# Flyback_SMPS.net
KiCad netlist of a schematic drawn in Altium Designer
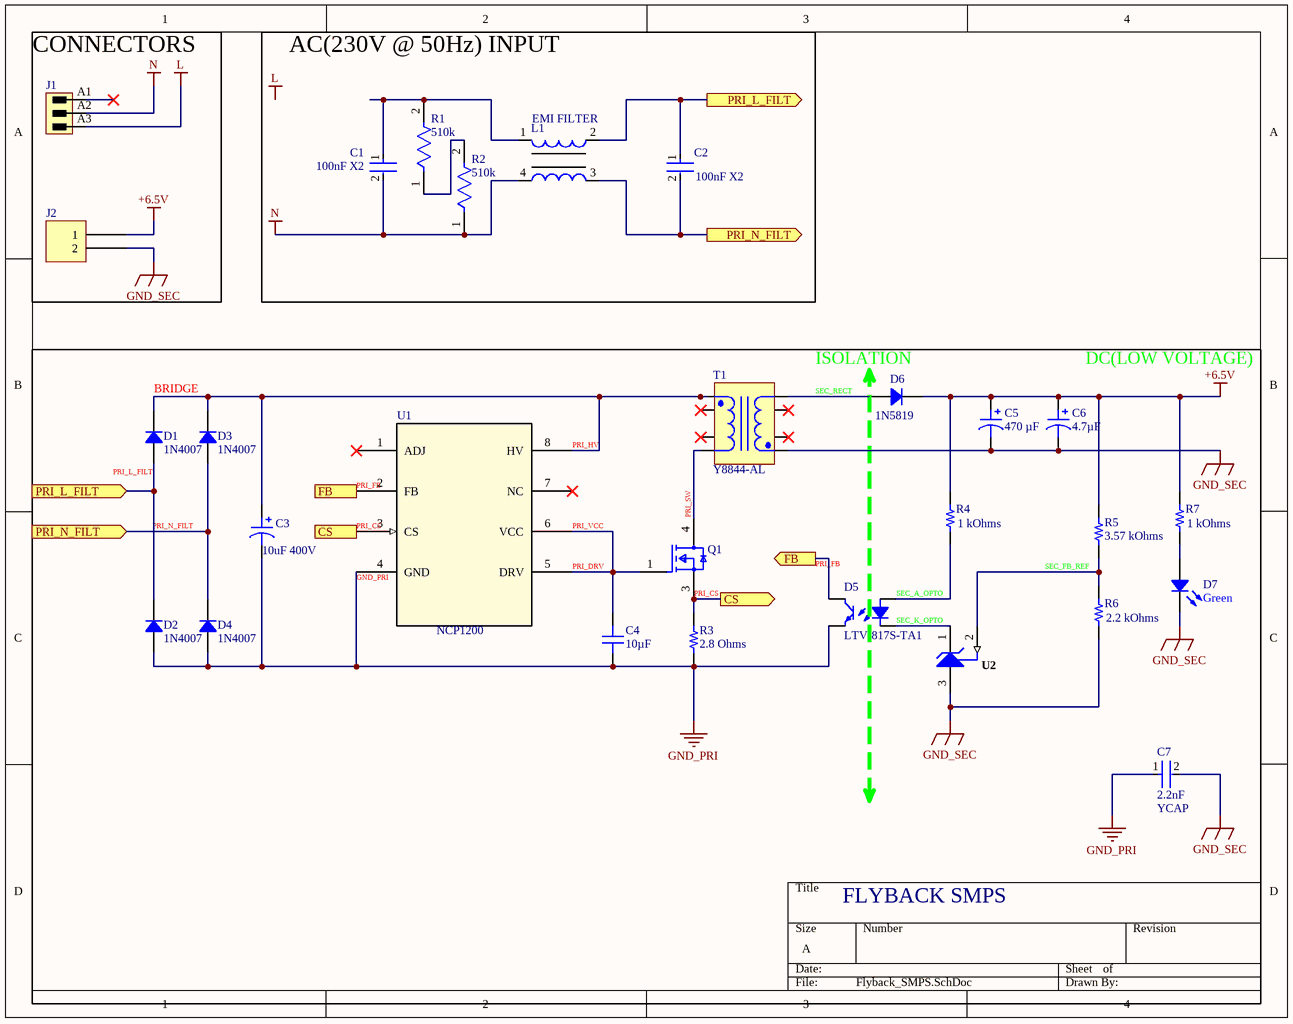
[diagram p0: Flyback_SMPS.SchDoc]

(export (version "E")
  (design (tool "Eeschema 10.0.6"))
  (components
    (comp (ref "C1")
      (value "100nF X2")
      (footprint "FP-R46KI3100JBM1K-MFG")
      (description "CAP FILM 0.1UF 10% 560VDC RADIAL")
      (fields (field (name "TOLERANCE") "10%"))
      (libsource (lib "Altium Content Vault") (part "b4654b650e69147ec39a6b967a45e02"))
    )
    (comp (ref "C2")
      (value "100nF X2")
      (footprint "FP-R46KI3100JBM1K-MFG")
      (description "CAP FILM 0.1UF 10% 560VDC RADIAL")
      (fields (field (name "TOLERANCE") "10%"))
      (libsource (lib "Altium Content Vault") (part "b4654b650e69147ec39a6b967a45e02"))
    )
    (comp (ref "C3")
      (value "10uF 400V")
      (footprint "CAP TH ALUM ELEC D10.00mm S5.00mm H17.50mm")
      (description "CAP 10 UF 20% 400 V")
      (fields (field (name "PART NUMBER") "860241375002") (field (name "MANUFACTURER") "Würth Elektronik"))
      (libsource (lib "Celestial Altium Library - altium_library") (part "Polarised Capacitor"))
    )
    (comp (ref "C4")
      (value "10µF")
      (footprint "CAP 1206_3216 - 1.8MM")
      (description "CAP CER 10UF 50V X5R 1206")
      (fields
        (field (name "PART NUMBER") "12065D106KAT2A")
        (field (name "CAPACITANCE") "10µF")
        (field (name "MANUFACTURER") "AVX Corporation")
      )
      (libsource (lib "Celestial Altium Library - altium_library") (part "Capacitor"))
    )
    (comp (ref "C5")
      (value "470 µF")
      (footprint "CAP AL TH D8 L3.5 H12.5")
      (description "CAP ALUM 470UF 20% 16V RADIAL")
      (fields (field (name "PART NUMBER") "UKW1C471MPD1TD") (field (name "MANUFACTURER") "Nichicon"))
      (libsource (lib "Celestial Altium Library - altium_library") (part "Polarised Capacitor"))
    )
    (comp (ref "C6")
      (value "4.7µF")
      (footprint "CAP TH ALUM ELEC D4.00mm S1.50mm H6.00mm")
      (description "CAP ALUM 4.7UF 20% 16V RADIAL")
      (fields (field (name "PART NUMBER") "UMP1C4R7MDD1TP") (field (name "MANUFACTURER") "Nichicon"))
      (libsource (lib "Celestial Altium Library - altium_library") (part "Polarised Capacitor"))
    )
    (comp (ref "C7")
      (value "YCAP")
      (footprint "Vishay_0_MFG")
      (description "2200 pF ±20% 500VAC Ceramic Capacitor Y5V (F) Radial, Disc")
      (fields
        (field (name "TOLERANCE") "20%")
        (field (name "MANUFACTURER") "Vishay")
        (field (name "ALTIUM_VALUE") "2.2nF")
      )
      (libsource (lib "Tiberiu's Altium Workspace") (part "VY1222M37Y5VQ63V0"))
    )
    (comp (ref "D1")
      (value "1N4007")
      (footprint "SOD123F")
      (description "STANDARD RECTIFIER 1000V SOD-123")
      (fields (field (name "PART NUMBER") "1N4007FLTR") (field (name "MANUFACTURER") "SMC Diode Solutions"))
      (libsource (lib "Celestial Altium Library - altium_library") (part "Diode"))
    )
    (comp (ref "D2")
      (value "1N4007")
      (footprint "SOD123F")
      (description "STANDARD RECTIFIER 1000V SOD-123")
      (fields (field (name "PART NUMBER") "1N4007FLTR") (field (name "MANUFACTURER") "SMC Diode Solutions"))
      (libsource (lib "Celestial Altium Library - altium_library") (part "Diode"))
    )
    (comp (ref "D3")
      (value "1N4007")
      (footprint "SOD123F")
      (description "STANDARD RECTIFIER 1000V SOD-123")
      (fields (field (name "PART NUMBER") "1N4007FLTR") (field (name "MANUFACTURER") "SMC Diode Solutions"))
      (libsource (lib "Celestial Altium Library - altium_library") (part "Diode"))
    )
    (comp (ref "D4")
      (value "1N4007")
      (footprint "SOD123F")
      (description "STANDARD RECTIFIER 1000V SOD-123")
      (fields (field (name "PART NUMBER") "1N4007FLTR") (field (name "MANUFACTURER") "SMC Diode Solutions"))
      (libsource (lib "Celestial Altium Library - altium_library") (part "Diode"))
    )
    (comp (ref "D5")
      (value "LTV-817S-TA1")
      (footprint "LITEON LTV-817")
      (description "OPTOISOLATR 5KV TRANSISTOR 4-SMD")
      (fields (field (name "MANUFACTURER") "Lite-On Inc."))
      (libsource (lib "Celestial Altium Library - altium_library") (part "Optoisolator"))
    )
    (comp (ref "D6")
      (value "1N5819")
      (footprint "SOD-123")
      (description "DIODE SCHOTTKY 40V 1A SOD123")
      (fields (field (name "PART NUMBER") "1N5819HW-7-F") (field (name "MANUFACTURER") "Diodes Incorporated"))
      (libsource (lib "Celestial Altium Library - altium_library") (part "Diode"))
    )
    (comp (ref "D7")
      (value "Green")
      (footprint "LED 0603_1608 GREEN")
      (description "NEXT GENERATION OF CHIP LED 0603")
      (fields
        (field (name "PART NUMBER") "LT Q99G.01-R2T1-25-1")
        (field (name "MANUFACTURER") "ams-OSRAM USA Inc.")
      )
      (libsource (lib "Celestial Altium Library - altium_library") (part "LED"))
    )
    (comp (ref "J1")
      (value "1146740000")
      (footprint "SL_5_08HC_90_03")
      (description "OMNIMATE Signal - series BL/SL 5.08")
      (fields (field (name "MANUFACTURER") "Weidmueller"))
      (libsource (lib "Altium Content Vault") (part "Header_Male_03_1x03"))
    )
    (comp (ref "J2")
      (value "282837-2")
      (footprint "TE 282837-2")
      (description "TERM BLK 2P SIDE ENT 5.08MM PCB")
      (fields (field (name "MANUFACTURER") "TE Connectivity AMP Connectors") (field (name "VOLTAGE") "300 V"))
      (libsource (lib "Celestial Altium Library - altium_library") (part "2 Pin"))
    )
    (comp (ref "L1")
      (value "744823305")
      (footprint "WE-CMB-M")
      (description "THT Common Mode Power Line Choke WE-CMB, L = 5.00 mH")
      (libsource (lib "transformer") (part "744823305"))
    )
    (comp (ref "Q1")
      (value "STD1NK60T4")
      (footprint "STMicroelectronics_DPAK_TO-252_-0068772_MFG")
      (description "N-Channel 600V 1A (Tc) 30W (Tc) Surface Mount DPAK")
      (fields
        (field (name "DIGIKEY PART NUMBER") "497-2483-1-ND")
        (field (name "MOUSER PART NUMBER") "511-STD1NK60")
      )
      (libsource (lib "Tiberiu's Altium Workspace") (part "STD1NK60T4"))
    )
    (comp (ref "R1")
      (value "510k")
      (footprint "FP-CR1206-IPC_A")
      (description "Thick Film Chip Resistors 1206 510kΩ 0.25W 5% 200ppm/°C")
      (fields (field (name "TOLERANCE") "5%"))
      (libsource (lib "Altium Content Vault") (part "1029c3af85768c4190bb7ad29bc67b5"))
    )
    (comp (ref "R2")
      (value "510k")
      (footprint "FP-CR1206-IPC_A")
      (description "Thick Film Chip Resistors 1206 510kΩ 0.25W 5% 200ppm/°C")
      (fields (field (name "TOLERANCE") "5%"))
      (libsource (lib "Altium Content Vault") (part "1029c3af85768c4190bb7ad29bc67b5"))
    )
    (comp (ref "R3")
      (value "2.8 Ohms")
      (footprint "RES 1206_3216")
      (description "CPF 1206 2R8 0.1% 25PPM 1K RL")
      (fields
        (field (name "PART NUMBER") "CPF1206B2R8E1")
        (field (name "MANUFACTURER") "TE Connectivity Passive Product")
      )
      (libsource (lib "Celestial Altium Library - altium_library") (part "Resistor"))
    )
    (comp (ref "R4")
      (value "1 kOhms")
      (footprint "RES 0402_1005")
      (description "RES SMD 1K OHM 0.1% 1/16W 0402")
      (fields
        (field (name "PART NUMBER") "CPF0402B1K0E")
        (field (name "MANUFACTURER") "TE Connectivity Passive Product")
      )
      (libsource (lib "Celestial Altium Library - altium_library") (part "Resistor"))
    )
    (comp (ref "R5")
      (value "3.57 kOhms")
      (footprint "YAGEO RES 1206_3216")
      (description "RES 3.57K OHM 1% 1/16W 0402")
      (fields (field (name "PART NUMBER") "RC0402FR-073K57L") (field (name "MANUFACTURER") "Yageo"))
      (libsource (lib "Celestial Altium Library - altium_library") (part "Resistor"))
    )
    (comp (ref "R6")
      (value "2.2 kOhms")
      (footprint "RES 0402_1005")
      (description "RES SMD 2.2K OHM 0.5% 1/16W 0402")
      (fields (field (name "PART NUMBER") "RR0510P-222-D") (field (name "MANUFACTURER") "Susumu"))
      (libsource (lib "Celestial Altium Library - altium_library") (part "Resistor"))
    )
    (comp (ref "R7")
      (value "1 kOhms")
      (footprint "RES 0402_1005")
      (description "RES SMD 1K OHM 0.1% 1/16W 0402")
      (fields
        (field (name "PART NUMBER") "CPF0402B1K0E")
        (field (name "MANUFACTURER") "TE Connectivity Passive Product")
      )
      (libsource (lib "Celestial Altium Library - altium_library") (part "Resistor"))
    )
    (comp (ref "T1")
      (value "Y8844-AL")
      (footprint "COIL-Y8844-AL-8_V")
      (description "Flyback Transformer, 3.5 W, -40 to 85 degC, 18.3 x 20.1 x 14 mm Package")
      (fields (field (name "MANUFACTURER") "Coilcraft"))
      (libsource (lib "transformer") (part "Y8844-AL"))
    )
    (comp (ref "U1")
      (value "NCP1200")
      (footprint "SOIC8_ONS")
      (description "No Description Available")
      (fields
        (field (name "MANUFACTURER_PART_NUMBER") "NCP1200AD100R2")
        (field (name "COPYRIGHT") "Copyright (C) 2025 Ultra Librarian. All rights reserved.")
      )
      (libsource (lib "transformer") (part "NCP1200AD100R2"))
    )
    (comp (ref "U2")
      (value "TL431AQDBZRQ1")
      (footprint "DBZ0003A_L")
      (fields (field (name "MANUFACTURER") "Texas Instruments"))
      (libsource (lib "transformer") (part "TL431AQDBZRQ1"))
    )
  )
  (nets
    (net (code "1") (name "+6.5V") (class "Default")
      (node (ref "C5") (pin "1") (pinfunction "1_1") (pintype "passive"))
      (node (ref "C6") (pin "1") (pinfunction "1_1") (pintype "passive"))
      (node (ref "D6") (pin "2") (pinfunction "2_2") (pintype "passive"))
      (node (ref "J2") (pin "1") (pinfunction "1_1") (pintype "passive"))
      (node (ref "R4") (pin "2") (pinfunction "2_2") (pintype "passive"))
      (node (ref "R5") (pin "2") (pinfunction "2_2") (pintype "passive"))
      (node (ref "R7") (pin "2") (pinfunction "2_2") (pintype "passive"))
    )
    (net (code "2") (name "/PRI_CS") (class "Default")
      (node (ref "Q1") (pin "3") (pinfunction "S_3") (pintype "passive"))
      (node (ref "R3") (pin "2") (pinfunction "2_2") (pintype "passive"))
      (node (ref "U1") (pin "3") (pinfunction "CS_3") (pintype "input"))
    )
    (net (code "3") (name "/PRI_DRV") (class "Default")
      (node (ref "C4") (pin "1") (pinfunction "1_1") (pintype "passive"))
      (node (ref "Q1") (pin "1") (pinfunction "G_1") (pintype "passive"))
      (node (ref "U1") (pin "5") (pinfunction "DRV_5") (pintype "passive"))
      (node (ref "U1") (pin "6") (pinfunction "VCC_6") (pintype "power_in"))
    )
    (net (code "4") (name "/PRI_FB") (class "Default")
      (node (ref "D5") (pin "4") (pinfunction "4_4") (pintype "passive"))
      (node (ref "U1") (pin "2") (pinfunction "FB_2") (pintype "passive"))
    )
    (net (code "5") (name "/PRI_HV") (class "Default")
      (node (ref "C3") (pin "1") (pinfunction "1_1") (pintype "passive"))
      (node (ref "D1") (pin "2") (pinfunction "2_2") (pintype "passive"))
      (node (ref "D3") (pin "2") (pinfunction "2_2") (pintype "passive"))
      (node (ref "T1") (pin "8") (pinfunction "8_8") (pintype "passive"))
      (node (ref "U1") (pin "8") (pinfunction "HV_8") (pintype "passive"))
    )
    (net (code "6") (name "/PRI_L_FILT") (class "Default")
      (node (ref "C2") (pin "1") (pinfunction "1_1") (pintype "passive"))
      (node (ref "D1") (pin "1") (pinfunction "1_1") (pintype "passive"))
      (node (ref "D2") (pin "2") (pinfunction "2_2") (pintype "passive"))
      (node (ref "L1") (pin "2") (pinfunction "2_2") (pintype "passive"))
    )
    (net (code "7") (name "/PRI_N_FILT") (class "Default")
      (node (ref "C2") (pin "2") (pinfunction "2_2") (pintype "passive"))
      (node (ref "D3") (pin "1") (pinfunction "1_1") (pintype "passive"))
      (node (ref "D4") (pin "2") (pinfunction "2_2") (pintype "passive"))
      (node (ref "L1") (pin "3") (pinfunction "3_3") (pintype "passive"))
    )
    (net (code "8") (name "/PRI_SW") (class "Default")
      (node (ref "Q1") (pin "4") (pinfunction "D_4") (pintype "passive"))
      (node (ref "T1") (pin "5") (pinfunction "5_5") (pintype "passive"))
    )
    (net (code "9") (name "/SEC_A_OPTO") (class "Default")
      (node (ref "D5") (pin "1") (pinfunction "1_1") (pintype "passive"))
      (node (ref "R4") (pin "1") (pinfunction "1_1") (pintype "passive"))
    )
    (net (code "10") (name "/SEC_FB_REF") (class "Default")
      (node (ref "R5") (pin "1") (pinfunction "1_1") (pintype "passive"))
      (node (ref "R6") (pin "2") (pinfunction "2_2") (pintype "passive"))
      (node (ref "U2") (pin "2") (pinfunction "REF_2") (pintype "input"))
    )
    (net (code "11") (name "/SEC_K_OPTO") (class "Default")
      (node (ref "D5") (pin "2") (pinfunction "2_2") (pintype "passive"))
      (node (ref "U2") (pin "1") (pinfunction "CATHODE_1") (pintype "passive"))
    )
    (net (code "12") (name "/SEC_RECT") (class "Default")
      (node (ref "D6") (pin "1") (pinfunction "1_1") (pintype "passive"))
      (node (ref "T1") (pin "4") (pinfunction "4_4") (pintype "passive"))
    )
    (net (code "13") (name "GND_PRI") (class "Default")
      (node (ref "C3") (pin "2") (pinfunction "2_2") (pintype "passive"))
      (node (ref "C4") (pin "2") (pinfunction "2_2") (pintype "passive"))
      (node (ref "C7") (pin "1") (pinfunction "1_1") (pintype "passive"))
      (node (ref "D2") (pin "1") (pinfunction "1_1") (pintype "passive"))
      (node (ref "D4") (pin "1") (pinfunction "1_1") (pintype "passive"))
      (node (ref "D5") (pin "3") (pinfunction "3_3") (pintype "passive"))
      (node (ref "R3") (pin "1") (pinfunction "1_1") (pintype "passive"))
      (node (ref "U1") (pin "4") (pinfunction "GND_4") (pintype "power_in"))
    )
    (net (code "14") (name "GND_SEC") (class "Default")
      (node (ref "C5") (pin "2") (pinfunction "2_2") (pintype "passive"))
      (node (ref "C6") (pin "2") (pinfunction "2_2") (pintype "passive"))
      (node (ref "C7") (pin "2") (pinfunction "2_2") (pintype "passive"))
      (node (ref "D7") (pin "2") (pinfunction "2_2") (pintype "passive"))
      (node (ref "J2") (pin "2") (pinfunction "2_2") (pintype "passive"))
      (node (ref "R6") (pin "1") (pinfunction "1_1") (pintype "passive"))
      (node (ref "T1") (pin "1") (pinfunction "1_1") (pintype "passive"))
      (node (ref "U2") (pin "3") (pinfunction "ANODE_3") (pintype "power_in"))
    )
    (net (code "15") (name "L") (class "Default")
      (node (ref "J1") (pin "A3") (pinfunction "A3_A3") (pintype "passive"))
    )
    (net (code "16") (name "N") (class "Default")
      (node (ref "C1") (pin "2") (pinfunction "2_2") (pintype "passive"))
      (node (ref "J1") (pin "A2") (pinfunction "A2_A2") (pintype "passive"))
      (node (ref "L1") (pin "4") (pinfunction "4_4") (pintype "passive"))
      (node (ref "R2") (pin "1") (pinfunction "1_1") (pintype "passive"))
    )
    (net (code "17") (name "Net-(C1-Pad1)") (class "Default")
      (node (ref "C1") (pin "1") (pinfunction "1_1") (pintype "passive"))
      (node (ref "L1") (pin "1") (pinfunction "1_1") (pintype "passive"))
      (node (ref "R1") (pin "2") (pinfunction "2_2") (pintype "passive"))
    )
    (net (code "18") (name "Net-(D7-Pad1)") (class "Default")
      (node (ref "D7") (pin "1") (pinfunction "1_1") (pintype "passive"))
      (node (ref "R7") (pin "1") (pinfunction "1_1") (pintype "passive"))
    )
    (net (code "19") (name "Net-(R1-Pad1)") (class "Default")
      (node (ref "R1") (pin "1") (pinfunction "1_1") (pintype "passive"))
      (node (ref "R2") (pin "2") (pinfunction "2_2") (pintype "passive"))
    )
    (net (code "20") (name "unconnected-(J1-PadA1)") (class "Default")
      (node (ref "J1") (pin "A1") (pinfunction "A1_A1") (pintype "passive+no_connect"))
    )
    (net (code "21") (name "unconnected-(T1-Pad2)") (class "Default")
      (node (ref "T1") (pin "2") (pinfunction "2_2") (pintype "passive+no_connect"))
    )
    (net (code "22") (name "unconnected-(T1-Pad3)") (class "Default")
      (node (ref "T1") (pin "3") (pinfunction "3_3") (pintype "passive+no_connect"))
    )
    (net (code "23") (name "unconnected-(T1-Pad6)") (class "Default")
      (node (ref "T1") (pin "6") (pinfunction "6_6") (pintype "passive+no_connect"))
    )
    (net (code "24") (name "unconnected-(T1-Pad7)") (class "Default")
      (node (ref "T1") (pin "7") (pinfunction "7_7") (pintype "passive+no_connect"))
    )
    (net (code "25") (name "unconnected-(U1-ADJ-Pad1)") (class "Default")
      (node (ref "U1") (pin "1") (pinfunction "ADJ_1") (pintype "passive+no_connect"))
    )
    (net (code "26") (name "unconnected-(U1-NC-Pad7)") (class "Default")
      (node (ref "U1") (pin "7") (pinfunction "NC_7") (pintype "passive+no_connect"))
    )
  )
)
